# Alarm_clock.net
KiCad netlist of a schematic drawn in EAGLE
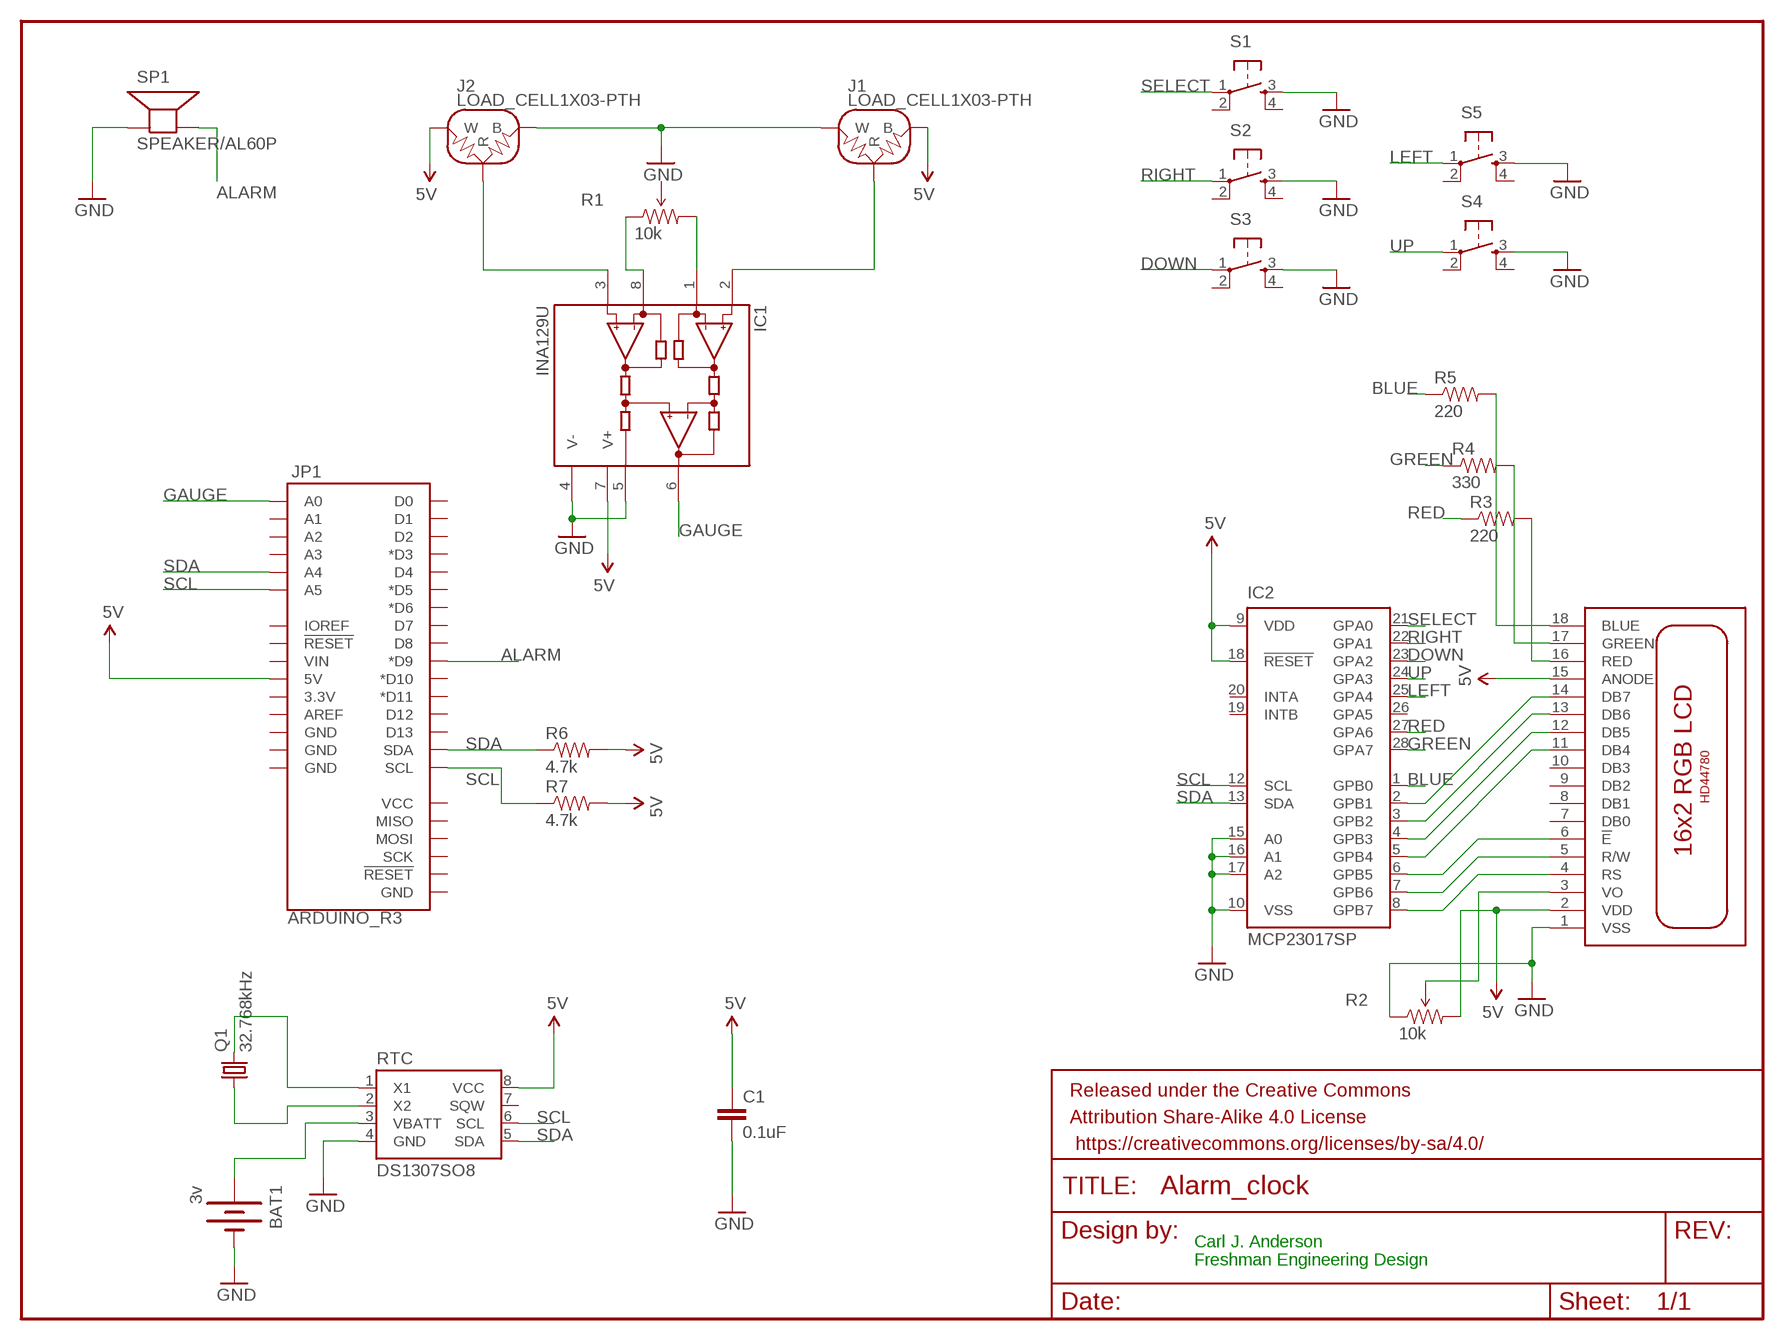
[diagram p0: schematic, sheet 1]

(export (version "E")
  (design (tool "Eeschema 10.0.6"))
  (components
    (comp (ref "BAT1")
      (value "3v")
      (footprint "eagle-import:BATTERY_20MM_PTH_COMPACT")
      (libsource (lib "eagle-import") (part "BATTERYFOB"))
    )
    (comp (ref "C1")
      (value "0.1uF")
      (footprint "eagle-import:0402-CAP")
      (libsource (lib "eagle-import") (part "0.1UF-16V(+-10%)(0402)"))
    )
    (comp (ref "FRAME1")
      (value "FRAME-LETTER")
      (footprint "eagle-import:CREATIVE_COMMONS")
      (libsource (lib "eagle-import") (part "FRAME-LETTER"))
    )
    (comp (ref "IC1")
      (value "INA129U")
      (footprint "eagle-import:SO08")
      (fields (field (name "MF") "TEXAS INSTRUMENTS"))
      (libsource (lib "eagle-import") (part "INA129U"))
    )
    (comp (ref "IC2")
      (value "MCP23017SP")
      (footprint "eagle-import:DIL28-3")
      (fields (field (name "MF") "MICROCHIP") (field (name "MPN") "MCP23017-E/SP"))
      (libsource (lib "eagle-import") (part "MCP23017SP"))
    )
    (comp (ref "J1")
      (value "LOAD_CELL1X03-PTH")
      (footprint "eagle-import:1X03")
      (libsource (lib "eagle-import") (part "LOAD_CELL1X03-PTH"))
    )
    (comp (ref "J2")
      (value "LOAD_CELL1X03-PTH")
      (footprint "eagle-import:1X03")
      (libsource (lib "eagle-import") (part "LOAD_CELL1X03-PTH"))
    )
    (comp (ref "JP1")
      (value "ARDUINO_R3")
      (footprint "eagle-import:ARDUINO_R3")
      (libsource (lib "eagle-import") (part "ARDUINO_R3"))
    )
    (comp (ref "Q1")
      (value "32.768kHz")
      (footprint "eagle-import:TC26H")
      (libsource (lib "eagle-import") (part "CRYSTALTC26H"))
    )
    (comp (ref "R1")
      (value "10k")
      (footprint "eagle-import:TRIMPOT-5MM-V2")
      (libsource (lib "eagle-import") (part "TRIMPOT"))
    )
    (comp (ref "R2")
      (value "10k")
      (footprint "eagle-import:TRIMPOT-5MM-V2")
      (libsource (lib "eagle-import") (part "TRIMPOT"))
    )
    (comp (ref "R3")
      (value "220")
      (footprint "eagle-import:AXIAL-0.4")
      (libsource (lib "eagle-import") (part "RESISTORPTH-1/4W"))
    )
    (comp (ref "R4")
      (value "330")
      (footprint "eagle-import:AXIAL-0.4")
      (libsource (lib "eagle-import") (part "RESISTORPTH-1/4W"))
    )
    (comp (ref "R5")
      (value "220")
      (footprint "eagle-import:AXIAL-0.4")
      (libsource (lib "eagle-import") (part "RESISTORPTH-1/4W"))
    )
    (comp (ref "R6")
      (value "4.7k")
      (footprint "eagle-import:AXIAL-0.4")
      (libsource (lib "eagle-import") (part "RESISTORPTH-1/4W"))
    )
    (comp (ref "R7")
      (value "4.7k")
      (footprint "eagle-import:AXIAL-0.4")
      (libsource (lib "eagle-import") (part "RESISTORPTH-1/4W"))
    )
    (comp (ref "RTC")
      (value "DS1307SO8")
      (footprint "eagle-import:SO08")
      (libsource (lib "eagle-import") (part "DS1307SO8"))
    )
    (comp (ref "S1")
      (value "TAC_SWITCHPTH")
      (footprint "eagle-import:TACTILE-PTH")
      (libsource (lib "eagle-import") (part "TAC_SWITCHPTH"))
    )
    (comp (ref "S2")
      (value "TAC_SWITCHPTH")
      (footprint "eagle-import:TACTILE-PTH")
      (libsource (lib "eagle-import") (part "TAC_SWITCHPTH"))
    )
    (comp (ref "S3")
      (value "TAC_SWITCHPTH")
      (footprint "eagle-import:TACTILE-PTH")
      (libsource (lib "eagle-import") (part "TAC_SWITCHPTH"))
    )
    (comp (ref "S4")
      (value "TAC_SWITCHPTH")
      (footprint "eagle-import:TACTILE-PTH")
      (libsource (lib "eagle-import") (part "TAC_SWITCHPTH"))
    )
    (comp (ref "S5")
      (value "TAC_SWITCHPTH")
      (footprint "eagle-import:TACTILE-PTH")
      (libsource (lib "eagle-import") (part "TAC_SWITCHPTH"))
    )
    (comp (ref "SP1")
      (value "SPEAKER/AL60P")
      (footprint "eagle-import:AL60P")
      (libsource (lib "eagle-import") (part "SPEAKER/AL60P"))
    )
    (comp (ref "U$1")
      (value "LCD16X2-RGB")
      (footprint "eagle-import:LCD16X2-RGB")
      (libsource (lib "eagle-import") (part "LCD16X2-RGB"))
    )
  )
  (nets
    (net (code "1") (name "/ALARM") (class "Default")
      (node (ref "JP1") (pin "D9") (pinfunction "*D9_D9") (pintype "bidirectional"))
      (node (ref "SP1") (pin "2") (pinfunction "-_2") (pintype "passive"))
    )
    (net (code "2") (name "/BLUE") (class "Default")
      (node (ref "IC2") (pin "1") (pinfunction "GPB0_1") (pintype "bidirectional"))
      (node (ref "R5") (pin "P$1") (pinfunction "1_P$1") (pintype "passive"))
    )
    (net (code "3") (name "/DOWN") (class "Default")
      (node (ref "IC2") (pin "23") (pinfunction "GPA2_23") (pintype "bidirectional"))
      (node (ref "S3") (pin "1") (pinfunction "1_1") (pintype "passive"))
    )
    (net (code "4") (name "/GAUGE") (class "Default")
      (node (ref "IC1") (pin "6") (pinfunction "OUT_6") (pintype "output"))
      (node (ref "JP1") (pin "A0") (pinfunction "A0_A0") (pintype "bidirectional"))
    )
    (net (code "5") (name "/GREEN") (class "Default")
      (node (ref "IC2") (pin "28") (pinfunction "GPA7_28") (pintype "bidirectional"))
      (node (ref "R4") (pin "P$1") (pinfunction "1_P$1") (pintype "passive"))
    )
    (net (code "6") (name "/LEFT") (class "Default")
      (node (ref "IC2") (pin "25") (pinfunction "GPA4_25") (pintype "bidirectional"))
      (node (ref "S5") (pin "1") (pinfunction "1_1") (pintype "passive"))
    )
    (net (code "7") (name "/RED") (class "Default")
      (node (ref "IC2") (pin "27") (pinfunction "GPA6_27") (pintype "bidirectional"))
      (node (ref "R3") (pin "P$1") (pinfunction "1_P$1") (pintype "passive"))
    )
    (net (code "8") (name "/RIGHT") (class "Default")
      (node (ref "IC2") (pin "22") (pinfunction "GPA1_22") (pintype "bidirectional"))
      (node (ref "S2") (pin "1") (pinfunction "1_1") (pintype "passive"))
    )
    (net (code "9") (name "/SCL") (class "Default")
      (node (ref "IC2") (pin "12") (pinfunction "SCL_12") (pintype "input"))
      (node (ref "JP1") (pin "A5") (pinfunction "A5_A5") (pintype "bidirectional"))
      (node (ref "JP1") (pin "SCL") (pinfunction "SCL_SCL") (pintype "bidirectional"))
      (node (ref "R7") (pin "P$1") (pinfunction "1_P$1") (pintype "passive"))
      (node (ref "RTC") (pin "6") (pinfunction "SCL_6") (pintype "bidirectional"))
    )
    (net (code "10") (name "/SDA") (class "Default")
      (node (ref "IC2") (pin "13") (pinfunction "SDA_13") (pintype "bidirectional"))
      (node (ref "JP1") (pin "A4") (pinfunction "A4_A4") (pintype "bidirectional"))
      (node (ref "JP1") (pin "SDA") (pinfunction "SDA_SDA") (pintype "bidirectional"))
      (node (ref "R6") (pin "P$1") (pinfunction "1_P$1") (pintype "passive"))
      (node (ref "RTC") (pin "5") (pinfunction "SDA_5") (pintype "bidirectional"))
    )
    (net (code "11") (name "/SELECT") (class "Default")
      (node (ref "IC2") (pin "21") (pinfunction "GPA0_21") (pintype "bidirectional"))
      (node (ref "S1") (pin "1") (pinfunction "1_1") (pintype "passive"))
    )
    (net (code "12") (name "/UP") (class "Default")
      (node (ref "IC2") (pin "24") (pinfunction "GPA3_24") (pintype "bidirectional"))
      (node (ref "S4") (pin "1") (pinfunction "1_1") (pintype "passive"))
    )
    (net (code "13") (name "5V") (class "Default")
      (node (ref "C1") (pin "1") (pinfunction "1_1") (pintype "passive"))
      (node (ref "IC1") (pin "7") (pinfunction "V+_7") (pintype "power_in"))
      (node (ref "IC2") (pin "18") (pinfunction "~{RESET}_18") (pintype "input"))
      (node (ref "IC2") (pin "9") (pinfunction "VDD_9") (pintype "power_in"))
      (node (ref "J1") (pin "1") (pinfunction "B_1") (pintype "passive"))
      (node (ref "J2") (pin "2") (pinfunction "W_2") (pintype "passive"))
      (node (ref "JP1") (pin "5V") (pinfunction "5V_5V") (pintype "bidirectional"))
      (node (ref "R2") (pin "C") (pinfunction "CW_C") (pintype "passive"))
      (node (ref "R6") (pin "P$2") (pinfunction "2_P$2") (pintype "passive"))
      (node (ref "R7") (pin "P$2") (pinfunction "2_P$2") (pintype "passive"))
      (node (ref "RTC") (pin "8") (pinfunction "VCC_8") (pintype "bidirectional"))
      (node (ref "U$1") (pin "15") (pinfunction "ANODE_15") (pintype "bidirectional"))
      (node (ref "U$1") (pin "2") (pinfunction "VDD_2") (pintype "bidirectional"))
    )
    (net (code "14") (name "GND") (class "Default")
      (node (ref "BAT1") (pin "2") (pinfunction "-_2") (pintype "power_in"))
      (node (ref "C1") (pin "2") (pinfunction "2_2") (pintype "passive"))
      (node (ref "IC1") (pin "4") (pinfunction "V-_4") (pintype "power_in"))
      (node (ref "IC1") (pin "5") (pinfunction "REF_5") (pintype "passive"))
      (node (ref "IC2") (pin "10") (pinfunction "VSS_10") (pintype "power_in"))
      (node (ref "IC2") (pin "15") (pinfunction "A0_15") (pintype "input"))
      (node (ref "IC2") (pin "16") (pinfunction "A1_16") (pintype "input"))
      (node (ref "IC2") (pin "17") (pinfunction "A2_17") (pintype "input"))
      (node (ref "J1") (pin "2") (pinfunction "W_2") (pintype "passive"))
      (node (ref "J2") (pin "1") (pinfunction "B_1") (pintype "passive"))
      (node (ref "R2") (pin "A") (pinfunction "CCW_A") (pintype "passive"))
      (node (ref "RTC") (pin "4") (pinfunction "GND_4") (pintype "bidirectional"))
      (node (ref "S1") (pin "3") (pinfunction "3_3") (pintype "passive"))
      (node (ref "S2") (pin "3") (pinfunction "3_3") (pintype "passive"))
      (node (ref "S3") (pin "3") (pinfunction "3_3") (pintype "passive"))
      (node (ref "S4") (pin "3") (pinfunction "3_3") (pintype "passive"))
      (node (ref "S5") (pin "3") (pinfunction "3_3") (pintype "passive"))
      (node (ref "SP1") (pin "1") (pinfunction "+_1") (pintype "passive"))
      (node (ref "U$1") (pin "1") (pinfunction "VSS_1") (pintype "bidirectional"))
    )
    (net (code "15") (name "Net-(BAT1-+)") (class "Default")
      (node (ref "BAT1") (pin "1") (pinfunction "+_1") (pintype "power_in"))
      (node (ref "RTC") (pin "3") (pinfunction "VBATT_3") (pintype "bidirectional"))
    )
    (net (code "16") (name "Net-(IC1-+IN)") (class "Default")
      (node (ref "IC1") (pin "3") (pinfunction "+IN_3") (pintype "input"))
      (node (ref "J2") (pin "3") (pinfunction "R_3") (pintype "passive"))
    )
    (net (code "17") (name "Net-(IC1--IN)") (class "Default")
      (node (ref "IC1") (pin "2") (pinfunction "-IN_2") (pintype "input"))
      (node (ref "J1") (pin "3") (pinfunction "R_3") (pintype "passive"))
    )
    (net (code "18") (name "Net-(IC2-GPB1)") (class "Default")
      (node (ref "IC2") (pin "2") (pinfunction "GPB1_2") (pintype "bidirectional"))
      (node (ref "U$1") (pin "14") (pinfunction "DB7_14") (pintype "bidirectional"))
    )
    (net (code "19") (name "Net-(IC2-GPB2)") (class "Default")
      (node (ref "IC2") (pin "3") (pinfunction "GPB2_3") (pintype "bidirectional"))
      (node (ref "U$1") (pin "13") (pinfunction "DB6_13") (pintype "bidirectional"))
    )
    (net (code "20") (name "Net-(IC2-GPB3)") (class "Default")
      (node (ref "IC2") (pin "4") (pinfunction "GPB3_4") (pintype "bidirectional"))
      (node (ref "U$1") (pin "12") (pinfunction "DB5_12") (pintype "bidirectional"))
    )
    (net (code "21") (name "Net-(IC2-GPB4)") (class "Default")
      (node (ref "IC2") (pin "5") (pinfunction "GPB4_5") (pintype "bidirectional"))
      (node (ref "U$1") (pin "11") (pinfunction "DB4_11") (pintype "bidirectional"))
    )
    (net (code "22") (name "Net-(IC2-GPB5)") (class "Default")
      (node (ref "IC2") (pin "6") (pinfunction "GPB5_6") (pintype "bidirectional"))
      (node (ref "U$1") (pin "6") (pinfunction "~{E}_6") (pintype "bidirectional"))
    )
    (net (code "23") (name "Net-(IC2-GPB6)") (class "Default")
      (node (ref "IC2") (pin "7") (pinfunction "GPB6_7") (pintype "bidirectional"))
      (node (ref "U$1") (pin "5") (pinfunction "R/W_5") (pintype "bidirectional"))
    )
    (net (code "24") (name "Net-(IC2-GPB7)") (class "Default")
      (node (ref "IC2") (pin "8") (pinfunction "GPB7_8") (pintype "bidirectional"))
      (node (ref "U$1") (pin "4") (pinfunction "RS_4") (pintype "bidirectional"))
    )
    (net (code "25") (name "Net-(R1-CCW)") (class "Default")
      (node (ref "IC1") (pin "8") (pinfunction "RG_8") (pintype "passive"))
      (node (ref "R1") (pin "A") (pinfunction "CCW_A") (pintype "passive"))
    )
    (net (code "26") (name "Net-(R1-CW)") (class "Default")
      (node (ref "IC1") (pin "1") (pinfunction "RG_1") (pintype "passive"))
      (node (ref "R1") (pin "C") (pinfunction "CW_C") (pintype "passive"))
    )
    (net (code "27") (name "Net-(R2-WIPER)") (class "Default")
      (node (ref "R2") (pin "B") (pinfunction "WIPER_B") (pintype "passive"))
      (node (ref "U$1") (pin "3") (pinfunction "VO_3") (pintype "bidirectional"))
    )
    (net (code "28") (name "Net-(R3-2)") (class "Default")
      (node (ref "R3") (pin "P$2") (pinfunction "2_P$2") (pintype "passive"))
      (node (ref "U$1") (pin "16") (pinfunction "RED_16") (pintype "bidirectional"))
    )
    (net (code "29") (name "Net-(R4-2)") (class "Default")
      (node (ref "R4") (pin "P$2") (pinfunction "2_P$2") (pintype "passive"))
      (node (ref "U$1") (pin "17") (pinfunction "GREEN_17") (pintype "bidirectional"))
    )
    (net (code "30") (name "Net-(R5-2)") (class "Default")
      (node (ref "R5") (pin "P$2") (pinfunction "2_P$2") (pintype "passive"))
      (node (ref "U$1") (pin "18") (pinfunction "BLUE_18") (pintype "bidirectional"))
    )
    (net (code "31") (name "Net-(RTC-X1)") (class "Default")
      (node (ref "Q1") (pin "2") (pinfunction "2_2") (pintype "passive"))
      (node (ref "RTC") (pin "1") (pinfunction "X1_1") (pintype "bidirectional"))
    )
    (net (code "32") (name "Net-(RTC-X2)") (class "Default")
      (node (ref "Q1") (pin "1") (pinfunction "1_1") (pintype "passive"))
      (node (ref "RTC") (pin "2") (pinfunction "X2_2") (pintype "bidirectional"))
    )
    (net (code "33") (name "unconnected-(IC2-GPA5-Pad26)") (class "Default")
      (node (ref "IC2") (pin "26") (pinfunction "GPA5_26") (pintype "bidirectional"))
    )
    (net (code "34") (name "unconnected-(IC2-INTA-Pad20)") (class "Default")
      (node (ref "IC2") (pin "20") (pinfunction "INTA_20") (pintype "output"))
    )
    (net (code "35") (name "unconnected-(IC2-INTB-Pad19)") (class "Default")
      (node (ref "IC2") (pin "19") (pinfunction "INTB_19") (pintype "output"))
    )
    (net (code "36") (name "unconnected-(JP1-*D3-PadD3)") (class "Default")
      (node (ref "JP1") (pin "D3") (pinfunction "*D3_D3") (pintype "bidirectional"))
    )
    (net (code "37") (name "unconnected-(JP1-*D5-PadD5)") (class "Default")
      (node (ref "JP1") (pin "D5") (pinfunction "*D5_D5") (pintype "bidirectional"))
    )
    (net (code "38") (name "unconnected-(JP1-*D6-PadD6)") (class "Default")
      (node (ref "JP1") (pin "D6") (pinfunction "*D6_D6") (pintype "bidirectional"))
    )
    (net (code "39") (name "unconnected-(JP1-*D10-PadD10)") (class "Default")
      (node (ref "JP1") (pin "D10") (pinfunction "*D10_D10") (pintype "bidirectional"))
    )
    (net (code "40") (name "unconnected-(JP1-*D11-PadD11)") (class "Default")
      (node (ref "JP1") (pin "D11") (pinfunction "*D11_D11") (pintype "bidirectional"))
    )
    (net (code "41") (name "unconnected-(JP1-GND-PadGND@1)") (class "Default")
      (node (ref "JP1") (pin "GND@1") (pinfunction "GND_GND@1") (pintype "bidirectional"))
    )
    (net (code "42") (name "unconnected-(JP1-GND-PadGND@2)") (class "Default")
      (node (ref "JP1") (pin "GND@2") (pinfunction "GND_GND@2") (pintype "bidirectional"))
    )
    (net (code "43") (name "unconnected-(JP1-GND-PadGND@3)") (class "Default")
      (node (ref "JP1") (pin "GND@3") (pinfunction "GND_GND@3") (pintype "bidirectional"))
    )
    (net (code "44") (name "unconnected-(JP1-GND-PadGND@4)") (class "Default")
      (node (ref "JP1") (pin "GND@4") (pinfunction "GND_GND@4") (pintype "bidirectional"))
    )
    (net (code "45") (name "unconnected-(JP1-Pad3.3V)") (class "Default")
      (node (ref "JP1") (pin "3.3V") (pinfunction "3.3V_3.3V") (pintype "bidirectional"))
    )
    (net (code "46") (name "unconnected-(JP1-PadA1)") (class "Default")
      (node (ref "JP1") (pin "A1") (pinfunction "A1_A1") (pintype "bidirectional"))
    )
    (net (code "47") (name "unconnected-(JP1-PadA2)") (class "Default")
      (node (ref "JP1") (pin "A2") (pinfunction "A2_A2") (pintype "bidirectional"))
    )
    (net (code "48") (name "unconnected-(JP1-PadA3)") (class "Default")
      (node (ref "JP1") (pin "A3") (pinfunction "A3_A3") (pintype "bidirectional"))
    )
    (net (code "49") (name "unconnected-(JP1-PadAREF)") (class "Default")
      (node (ref "JP1") (pin "AREF") (pinfunction "AREF_AREF") (pintype "bidirectional"))
    )
    (net (code "50") (name "unconnected-(JP1-PadD0)") (class "Default")
      (node (ref "JP1") (pin "D0") (pinfunction "D0_D0") (pintype "bidirectional"))
    )
    (net (code "51") (name "unconnected-(JP1-PadD1)") (class "Default")
      (node (ref "JP1") (pin "D1") (pinfunction "D1_D1") (pintype "bidirectional"))
    )
    (net (code "52") (name "unconnected-(JP1-PadD2)") (class "Default")
      (node (ref "JP1") (pin "D2") (pinfunction "D2_D2") (pintype "bidirectional"))
    )
    (net (code "53") (name "unconnected-(JP1-PadD4)") (class "Default")
      (node (ref "JP1") (pin "D4") (pinfunction "D4_D4") (pintype "bidirectional"))
    )
    (net (code "54") (name "unconnected-(JP1-PadD7)") (class "Default")
      (node (ref "JP1") (pin "D7") (pinfunction "D7_D7") (pintype "bidirectional"))
    )
    (net (code "55") (name "unconnected-(JP1-PadD8)") (class "Default")
      (node (ref "JP1") (pin "D8") (pinfunction "D8_D8") (pintype "bidirectional"))
    )
    (net (code "56") (name "unconnected-(JP1-PadD12)") (class "Default")
      (node (ref "JP1") (pin "D12") (pinfunction "D12_D12") (pintype "bidirectional"))
    )
    (net (code "57") (name "unconnected-(JP1-PadD13)") (class "Default")
      (node (ref "JP1") (pin "D13") (pinfunction "D13_D13") (pintype "bidirectional"))
    )
    (net (code "58") (name "unconnected-(JP1-PadIOREF)") (class "Default")
      (node (ref "JP1") (pin "IOREF") (pinfunction "IOREF_IOREF") (pintype "bidirectional"))
    )
    (net (code "59") (name "unconnected-(JP1-PadMISO)") (class "Default")
      (node (ref "JP1") (pin "MISO") (pinfunction "MISO_MISO") (pintype "bidirectional"))
    )
    (net (code "60") (name "unconnected-(JP1-PadMOSI)") (class "Default")
      (node (ref "JP1") (pin "MOSI") (pinfunction "MOSI_MOSI") (pintype "bidirectional"))
    )
    (net (code "61") (name "unconnected-(JP1-PadSCK)") (class "Default")
      (node (ref "JP1") (pin "SCK") (pinfunction "SCK_SCK") (pintype "bidirectional"))
    )
    (net (code "62") (name "unconnected-(JP1-PadVCC)") (class "Default")
      (node (ref "JP1") (pin "VCC") (pinfunction "VCC_VCC") (pintype "bidirectional"))
    )
    (net (code "63") (name "unconnected-(JP1-PadVIN)") (class "Default")
      (node (ref "JP1") (pin "VIN") (pinfunction "VIN_VIN") (pintype "bidirectional"))
    )
    (net (code "64") (name "unconnected-(JP1-~{RESET}-PadRESET@1)") (class "Default")
      (node (ref "JP1") (pin "RESET@1") (pinfunction "~{RESET}_RESET@1") (pintype "bidirectional"))
    )
    (net (code "65") (name "unconnected-(JP1-~{RESET}-PadRESET@2)") (class "Default")
      (node (ref "JP1") (pin "RESET@2") (pinfunction "~{RESET}_RESET@2") (pintype "bidirectional"))
    )
    (net (code "66") (name "unconnected-(R1-WIPER-PadB)") (class "Default")
      (node (ref "R1") (pin "B") (pinfunction "WIPER_B") (pintype "passive"))
    )
    (net (code "67") (name "unconnected-(RTC-SQW-Pad7)") (class "Default")
      (node (ref "RTC") (pin "7") (pinfunction "SQW_7") (pintype "bidirectional"))
    )
    (net (code "68") (name "unconnected-(S1-Pad2)") (class "Default")
      (node (ref "S1") (pin "2") (pinfunction "2_2") (pintype "passive"))
    )
    (net (code "69") (name "unconnected-(S1-Pad4)") (class "Default")
      (node (ref "S1") (pin "4") (pinfunction "4_4") (pintype "passive"))
    )
    (net (code "70") (name "unconnected-(S2-Pad2)") (class "Default")
      (node (ref "S2") (pin "2") (pinfunction "2_2") (pintype "passive"))
    )
    (net (code "71") (name "unconnected-(S2-Pad4)") (class "Default")
      (node (ref "S2") (pin "4") (pinfunction "4_4") (pintype "passive"))
    )
    (net (code "72") (name "unconnected-(S3-Pad2)") (class "Default")
      (node (ref "S3") (pin "2") (pinfunction "2_2") (pintype "passive"))
    )
    (net (code "73") (name "unconnected-(S3-Pad4)") (class "Default")
      (node (ref "S3") (pin "4") (pinfunction "4_4") (pintype "passive"))
    )
    (net (code "74") (name "unconnected-(S4-Pad2)") (class "Default")
      (node (ref "S4") (pin "2") (pinfunction "2_2") (pintype "passive"))
    )
    (net (code "75") (name "unconnected-(S4-Pad4)") (class "Default")
      (node (ref "S4") (pin "4") (pinfunction "4_4") (pintype "passive"))
    )
    (net (code "76") (name "unconnected-(S5-Pad2)") (class "Default")
      (node (ref "S5") (pin "2") (pinfunction "2_2") (pintype "passive"))
    )
    (net (code "77") (name "unconnected-(S5-Pad4)") (class "Default")
      (node (ref "S5") (pin "4") (pinfunction "4_4") (pintype "passive"))
    )
    (net (code "78") (name "unconnected-(U$1-DB0-Pad7)") (class "Default")
      (node (ref "U$1") (pin "7") (pinfunction "DB0_7") (pintype "bidirectional"))
    )
    (net (code "79") (name "unconnected-(U$1-DB1-Pad8)") (class "Default")
      (node (ref "U$1") (pin "8") (pinfunction "DB1_8") (pintype "bidirectional"))
    )
    (net (code "80") (name "unconnected-(U$1-DB2-Pad9)") (class "Default")
      (node (ref "U$1") (pin "9") (pinfunction "DB2_9") (pintype "bidirectional"))
    )
    (net (code "81") (name "unconnected-(U$1-DB3-Pad10)") (class "Default")
      (node (ref "U$1") (pin "10") (pinfunction "DB3_10") (pintype "bidirectional"))
    )
  )
)
